# IGBT_C.net
KiCad netlist of a schematic drawn in Altium Designer
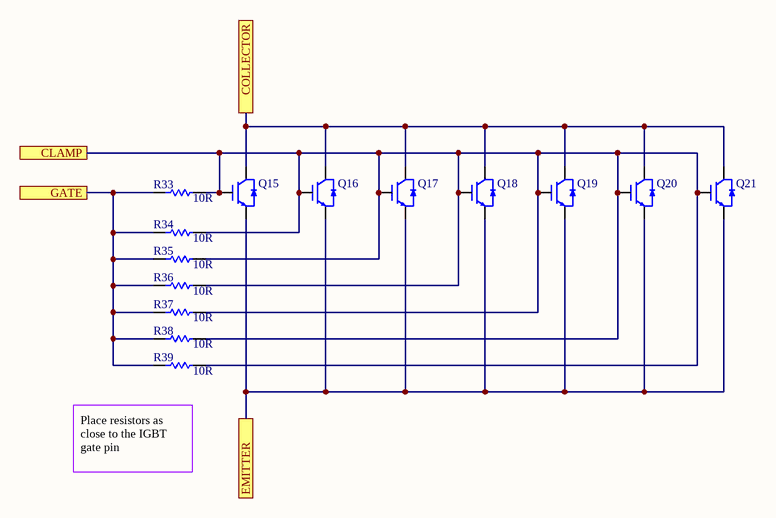
[diagram p0: IGBT_C.SchDoc]

(export (version "E")
  (design (tool "Eeschema 10.0.6"))
  (components
    (comp (ref "Q15")
      (value "STGB30V60DF")
      (footprint "DPAK2_IGBT")
      (description "IGBT 600V 60A 258W D2PAK")
      (fields (field (name "MANUFACTURER") "STMicroelectronics"))
      (libsource (lib "InverterSCHLib") (part "STGB30V60DF"))
    )
    (comp (ref "Q16")
      (value "STGB30V60DF")
      (footprint "DPAK2_IGBT")
      (description "IGBT 600V 60A 258W D2PAK")
      (fields (field (name "MANUFACTURER") "STMicroelectronics"))
      (libsource (lib "InverterSCHLib") (part "STGB30V60DF"))
    )
    (comp (ref "Q17")
      (value "STGB30V60DF")
      (footprint "DPAK2_IGBT")
      (description "IGBT 600V 60A 258W D2PAK")
      (fields (field (name "MANUFACTURER") "STMicroelectronics"))
      (libsource (lib "InverterSCHLib") (part "STGB30V60DF"))
    )
    (comp (ref "Q18")
      (value "STGB30V60DF")
      (footprint "DPAK2_IGBT")
      (description "IGBT 600V 60A 258W D2PAK")
      (fields (field (name "MANUFACTURER") "STMicroelectronics"))
      (libsource (lib "InverterSCHLib") (part "STGB30V60DF"))
    )
    (comp (ref "Q19")
      (value "STGB30V60DF")
      (footprint "DPAK2_IGBT")
      (description "IGBT 600V 60A 258W D2PAK")
      (fields (field (name "MANUFACTURER") "STMicroelectronics"))
      (libsource (lib "InverterSCHLib") (part "STGB30V60DF"))
    )
    (comp (ref "Q20")
      (value "STGB30V60DF")
      (footprint "DPAK2_IGBT")
      (description "IGBT 600V 60A 258W D2PAK")
      (fields (field (name "MANUFACTURER") "STMicroelectronics"))
      (libsource (lib "InverterSCHLib") (part "STGB30V60DF"))
    )
    (comp (ref "Q21")
      (value "STGB30V60DF")
      (footprint "DPAK2_IGBT")
      (description "IGBT 600V 60A 258W D2PAK")
      (fields (field (name "MANUFACTURER") "STMicroelectronics"))
      (libsource (lib "InverterSCHLib") (part "STGB30V60DF"))
    )
    (comp (ref "R33")
      (value "10R")
      (footprint "RES-0603")
      (description "RES SMD 10 OHM 1% 1/10W 0603")
      (fields
        (field (name "MANUFACTURER") "Yageo")
        (field (name "MANUFACTURER PART NUMBER") "RC0603FR-0710RL")
      )
      (libsource (lib "InverterSCHLib") (part "0603-10R"))
    )
    (comp (ref "R34")
      (value "10R")
      (footprint "RES-0603")
      (description "RES SMD 10 OHM 1% 1/10W 0603")
      (fields
        (field (name "MANUFACTURER") "Yageo")
        (field (name "MANUFACTURER PART NUMBER") "RC0603FR-0710RL")
      )
      (libsource (lib "InverterSCHLib") (part "0603-10R"))
    )
    (comp (ref "R35")
      (value "10R")
      (footprint "RES-0603")
      (description "RES SMD 10 OHM 1% 1/10W 0603")
      (fields
        (field (name "MANUFACTURER") "Yageo")
        (field (name "MANUFACTURER PART NUMBER") "RC0603FR-0710RL")
      )
      (libsource (lib "InverterSCHLib") (part "0603-10R"))
    )
    (comp (ref "R36")
      (value "10R")
      (footprint "RES-0603")
      (description "RES SMD 10 OHM 1% 1/10W 0603")
      (fields
        (field (name "MANUFACTURER") "Yageo")
        (field (name "MANUFACTURER PART NUMBER") "RC0603FR-0710RL")
      )
      (libsource (lib "InverterSCHLib") (part "0603-10R"))
    )
    (comp (ref "R37")
      (value "10R")
      (footprint "RES-0603")
      (description "RES SMD 10 OHM 1% 1/10W 0603")
      (fields
        (field (name "MANUFACTURER") "Yageo")
        (field (name "MANUFACTURER PART NUMBER") "RC0603FR-0710RL")
      )
      (libsource (lib "InverterSCHLib") (part "0603-10R"))
    )
    (comp (ref "R38")
      (value "10R")
      (footprint "RES-0603")
      (description "RES SMD 10 OHM 1% 1/10W 0603")
      (fields
        (field (name "MANUFACTURER") "Yageo")
        (field (name "MANUFACTURER PART NUMBER") "RC0603FR-0710RL")
      )
      (libsource (lib "InverterSCHLib") (part "0603-10R"))
    )
    (comp (ref "R39")
      (value "10R")
      (footprint "RES-0603")
      (description "RES SMD 10 OHM 1% 1/10W 0603")
      (fields
        (field (name "MANUFACTURER") "Yageo")
        (field (name "MANUFACTURER PART NUMBER") "RC0603FR-0710RL")
      )
      (libsource (lib "InverterSCHLib") (part "0603-10R"))
    )
  )
  (nets
    (net (code "1") (name "/CLAMP") (class "Default")
      (node (ref "Q15") (pin "1") (pinfunction "1_1") (pintype "passive"))
      (node (ref "Q16") (pin "1") (pinfunction "1_1") (pintype "passive"))
      (node (ref "Q17") (pin "1") (pinfunction "1_1") (pintype "passive"))
      (node (ref "Q18") (pin "1") (pinfunction "1_1") (pintype "passive"))
      (node (ref "Q19") (pin "1") (pinfunction "1_1") (pintype "passive"))
      (node (ref "Q20") (pin "1") (pinfunction "1_1") (pintype "passive"))
      (node (ref "Q21") (pin "1") (pinfunction "1_1") (pintype "passive"))
      (node (ref "R33") (pin "2") (pinfunction "2_2") (pintype "passive"))
      (node (ref "R34") (pin "2") (pinfunction "2_2") (pintype "passive"))
      (node (ref "R35") (pin "2") (pinfunction "2_2") (pintype "passive"))
      (node (ref "R36") (pin "2") (pinfunction "2_2") (pintype "passive"))
      (node (ref "R37") (pin "2") (pinfunction "2_2") (pintype "passive"))
      (node (ref "R38") (pin "2") (pinfunction "2_2") (pintype "passive"))
      (node (ref "R39") (pin "2") (pinfunction "2_2") (pintype "passive"))
    )
    (net (code "2") (name "/COLLECTOR") (class "Default")
      (node (ref "Q15") (pin "2") (pinfunction "2_2") (pintype "passive"))
      (node (ref "Q16") (pin "2") (pinfunction "2_2") (pintype "passive"))
      (node (ref "Q17") (pin "2") (pinfunction "2_2") (pintype "passive"))
      (node (ref "Q18") (pin "2") (pinfunction "2_2") (pintype "passive"))
      (node (ref "Q19") (pin "2") (pinfunction "2_2") (pintype "passive"))
      (node (ref "Q20") (pin "2") (pinfunction "2_2") (pintype "passive"))
      (node (ref "Q21") (pin "2") (pinfunction "2_2") (pintype "passive"))
    )
    (net (code "3") (name "/EMITTER") (class "Default")
      (node (ref "Q15") (pin "3") (pinfunction "3_3") (pintype "passive"))
      (node (ref "Q16") (pin "3") (pinfunction "3_3") (pintype "passive"))
      (node (ref "Q17") (pin "3") (pinfunction "3_3") (pintype "passive"))
      (node (ref "Q18") (pin "3") (pinfunction "3_3") (pintype "passive"))
      (node (ref "Q19") (pin "3") (pinfunction "3_3") (pintype "passive"))
      (node (ref "Q20") (pin "3") (pinfunction "3_3") (pintype "passive"))
      (node (ref "Q21") (pin "3") (pinfunction "3_3") (pintype "passive"))
    )
    (net (code "4") (name "/GATE") (class "Default")
      (node (ref "R33") (pin "1") (pinfunction "1_1") (pintype "passive"))
      (node (ref "R34") (pin "1") (pinfunction "1_1") (pintype "passive"))
      (node (ref "R35") (pin "1") (pinfunction "1_1") (pintype "passive"))
      (node (ref "R36") (pin "1") (pinfunction "1_1") (pintype "passive"))
      (node (ref "R37") (pin "1") (pinfunction "1_1") (pintype "passive"))
      (node (ref "R38") (pin "1") (pinfunction "1_1") (pintype "passive"))
      (node (ref "R39") (pin "1") (pinfunction "1_1") (pintype "passive"))
    )
  )
)
